# attiny85_0812_2016.net
KiCad netlist of a schematic drawn in EAGLE
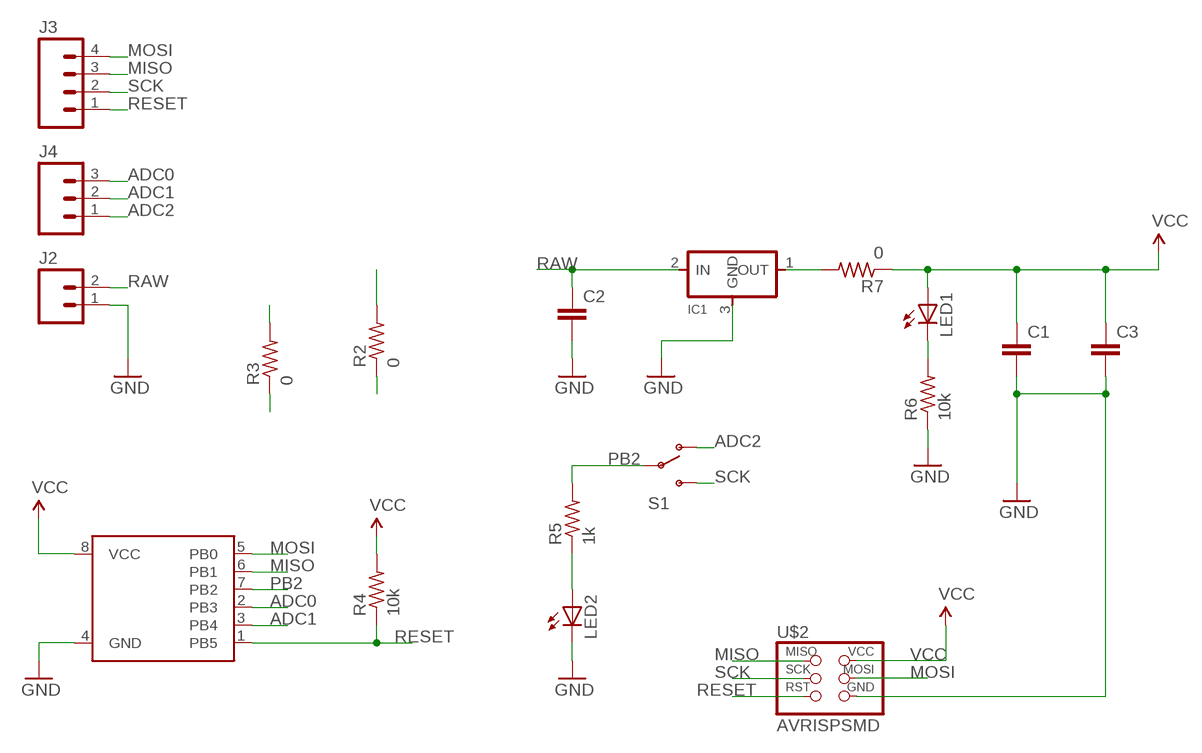
[diagram p0: schematic, sheet 1]

(export (version "E")
  (design (tool "Eeschema 10.0.6"))
  (components
    (comp (ref "C1")
      (value "CAP1206")
      (footprint "eagle-import:1206")
      (libsource (lib "eagle-import") (part "CAP1206"))
    )
    (comp (ref "C2")
      (value "CAP1206")
      (footprint "eagle-import:1206")
      (libsource (lib "eagle-import") (part "CAP1206"))
    )
    (comp (ref "C3")
      (value "CAP1206")
      (footprint "eagle-import:1206")
      (libsource (lib "eagle-import") (part "CAP1206"))
    )
    (comp (ref "IC1")
      (value "REGULATORSOT23")
      (footprint "eagle-import:SOT23")
      (libsource (lib "eagle-import") (part "REGULATORSOT23"))
    )
    (comp (ref "J2")
      (value "M02PTH")
      (footprint "eagle-import:1X02")
      (libsource (lib "eagle-import") (part "M02PTH"))
    )
    (comp (ref "J3")
      (value "M04NO_SILK_ALL_ROUND")
      (footprint "eagle-import:1X04_NO_SILK_ALL_ROUND")
      (libsource (lib "eagle-import") (part "M04NO_SILK_ALL_ROUND"))
    )
    (comp (ref "J4")
      (value "M03PTH")
      (footprint "eagle-import:1X03")
      (libsource (lib "eagle-import") (part "M03PTH"))
    )
    (comp (ref "LED1")
      (value "LEDCHIPLED_1206")
      (footprint "eagle-import:CHIPLED_1206")
      (libsource (lib "eagle-import") (part "LEDCHIPLED_1206"))
    )
    (comp (ref "LED2")
      (value "LEDCHIPLED_1206")
      (footprint "eagle-import:CHIPLED_1206")
      (libsource (lib "eagle-import") (part "LEDCHIPLED_1206"))
    )
    (comp (ref "R2")
      (value "0")
      (footprint "eagle-import:R1206FAB")
      (libsource (lib "eagle-import") (part "RES-US1206FAB"))
    )
    (comp (ref "R3")
      (value "0")
      (footprint "eagle-import:R1206FAB")
      (libsource (lib "eagle-import") (part "RES-US1206FAB"))
    )
    (comp (ref "R4")
      (value "10k")
      (footprint "eagle-import:R1206FAB")
      (libsource (lib "eagle-import") (part "RES-US1206FAB"))
    )
    (comp (ref "R5")
      (value "1k")
      (footprint "eagle-import:R1206FAB")
      (libsource (lib "eagle-import") (part "RES-US1206FAB"))
    )
    (comp (ref "R6")
      (value "10k")
      (footprint "eagle-import:R1206FAB")
      (libsource (lib "eagle-import") (part "RES-US1206FAB"))
    )
    (comp (ref "R7")
      (value "0")
      (footprint "eagle-import:R1206FAB")
      (libsource (lib "eagle-import") (part "RES-US1206FAB"))
    )
    (comp (ref "S1")
      (value "SWITCH-SPDTPTH")
      (footprint "eagle-import:SWITCH-SPDT")
      (libsource (lib "eagle-import") (part "SWITCH-SPDTPTH"))
    )
    (comp (ref "U$1")
      (value "ATTINY85EIAJ")
      (footprint "eagle-import:8S2_EIAJ-85")
      (libsource (lib "eagle-import") (part "ATTINY85EIAJ"))
    )
    (comp (ref "U$2")
      (value "AVRISPSMD")
      (footprint "eagle-import:2X03SMD")
      (libsource (lib "eagle-import") (part "AVRISPSMD"))
    )
  )
  (nets
    (net (code "1") (name "/ADC0") (class "Default")
      (node (ref "J4") (pin "3") (pinfunction "3_3") (pintype "passive"))
      (node (ref "U$1") (pin "2") (pinfunction "PB3_2") (pintype "bidirectional"))
    )
    (net (code "2") (name "/ADC1") (class "Default")
      (node (ref "J4") (pin "2") (pinfunction "2_2") (pintype "passive"))
      (node (ref "U$1") (pin "3") (pinfunction "PB4_3") (pintype "bidirectional"))
    )
    (net (code "3") (name "/ADC2") (class "Default")
      (node (ref "J4") (pin "1") (pinfunction "1_1") (pintype "passive"))
      (node (ref "S1") (pin "1") (pinfunction "O_1") (pintype "passive"))
    )
    (net (code "4") (name "/MISO") (class "Default")
      (node (ref "J3") (pin "3") (pinfunction "3_3") (pintype "passive"))
      (node (ref "U$1") (pin "6") (pinfunction "PB1_6") (pintype "bidirectional"))
      (node (ref "U$2") (pin "1") (pinfunction "MISO_1") (pintype "passive"))
    )
    (net (code "5") (name "/MOSI") (class "Default")
      (node (ref "J3") (pin "4") (pinfunction "4_4") (pintype "passive"))
      (node (ref "R3") (pin "1") (pinfunction "1_1") (pintype "passive"))
      (node (ref "R3") (pin "2") (pinfunction "2_2") (pintype "passive"))
      (node (ref "U$1") (pin "5") (pinfunction "PB0_5") (pintype "bidirectional"))
      (node (ref "U$2") (pin "4") (pinfunction "MOSI_4") (pintype "passive"))
    )
    (net (code "6") (name "/PB2") (class "Default")
      (node (ref "R5") (pin "2") (pinfunction "2_2") (pintype "passive"))
      (node (ref "S1") (pin "2") (pinfunction "P_2") (pintype "passive"))
      (node (ref "U$1") (pin "7") (pinfunction "PB2_7") (pintype "bidirectional"))
    )
    (net (code "7") (name "/RAW") (class "Default")
      (node (ref "C2") (pin "1") (pinfunction "1_1") (pintype "passive"))
      (node (ref "IC1") (pin "2") (pinfunction "IN_2") (pintype "bidirectional"))
      (node (ref "J2") (pin "2") (pinfunction "2_2") (pintype "passive"))
    )
    (net (code "8") (name "/RESET") (class "Default")
      (node (ref "J3") (pin "1") (pinfunction "1_1") (pintype "passive"))
      (node (ref "R4") (pin "1") (pinfunction "1_1") (pintype "passive"))
      (node (ref "U$1") (pin "1") (pinfunction "PB5_1") (pintype "bidirectional"))
      (node (ref "U$2") (pin "5") (pinfunction "RST_5") (pintype "passive"))
    )
    (net (code "9") (name "/SCK") (class "Default")
      (node (ref "J3") (pin "2") (pinfunction "2_2") (pintype "passive"))
      (node (ref "S1") (pin "3") (pinfunction "S_3") (pintype "passive"))
      (node (ref "U$2") (pin "3") (pinfunction "SCK_3") (pintype "passive"))
    )
    (net (code "10") (name "GND") (class "Default")
      (node (ref "C1") (pin "2") (pinfunction "2_2") (pintype "passive"))
      (node (ref "C2") (pin "2") (pinfunction "2_2") (pintype "passive"))
      (node (ref "C3") (pin "2") (pinfunction "2_2") (pintype "passive"))
      (node (ref "IC1") (pin "3") (pinfunction "GND_3") (pintype "bidirectional"))
      (node (ref "J2") (pin "1") (pinfunction "1_1") (pintype "passive"))
      (node (ref "LED2") (pin "C") (pinfunction "C_C") (pintype "passive"))
      (node (ref "R6") (pin "1") (pinfunction "1_1") (pintype "passive"))
      (node (ref "U$1") (pin "4") (pinfunction "GND_4") (pintype "power_in"))
      (node (ref "U$2") (pin "6") (pinfunction "GND_6") (pintype "passive"))
    )
    (net (code "11") (name "Net-(IC1-OUT)") (class "Default")
      (node (ref "IC1") (pin "1") (pinfunction "OUT_1") (pintype "bidirectional"))
      (node (ref "R7") (pin "2") (pinfunction "2_2") (pintype "passive"))
    )
    (net (code "12") (name "Net-(LED1-PadC)") (class "Default")
      (node (ref "LED1") (pin "C") (pinfunction "C_C") (pintype "passive"))
      (node (ref "R6") (pin "2") (pinfunction "2_2") (pintype "passive"))
    )
    (net (code "13") (name "Net-(LED2-PadA)") (class "Default")
      (node (ref "LED2") (pin "A") (pinfunction "A_A") (pintype "passive"))
      (node (ref "R5") (pin "1") (pinfunction "1_1") (pintype "passive"))
    )
    (net (code "14") (name "VCC") (class "Default")
      (node (ref "C1") (pin "1") (pinfunction "1_1") (pintype "passive"))
      (node (ref "C3") (pin "1") (pinfunction "1_1") (pintype "passive"))
      (node (ref "LED1") (pin "A") (pinfunction "A_A") (pintype "passive"))
      (node (ref "R2") (pin "1") (pinfunction "1_1") (pintype "passive"))
      (node (ref "R2") (pin "2") (pinfunction "2_2") (pintype "passive"))
      (node (ref "R4") (pin "2") (pinfunction "2_2") (pintype "passive"))
      (node (ref "R7") (pin "1") (pinfunction "1_1") (pintype "passive"))
      (node (ref "U$1") (pin "8") (pinfunction "VCC_8") (pintype "power_in"))
      (node (ref "U$2") (pin "2") (pinfunction "VCC_2") (pintype "passive"))
    )
  )
)
